# CAN_IC.net
KiCad netlist of a schematic drawn in Altium Designer
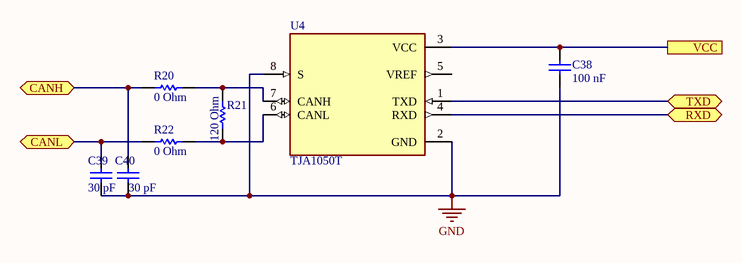
[diagram p0: CAN_IC.SchDoc]

(export (version "E")
  (design (tool "Eeschema 10.0.6"))
  (components
    (comp (ref "C38")
      (value "100 nF")
      (footprint "CAP_0603")
      (description "CAP, size 0603, 100 nF, 50 VDC")
      (fields (field (name "TOLERANCE") "+/-10%"))
      (libsource (lib "Altium_Ceramic_Cap") (part "0106031041050"))
    )
    (comp (ref "C39")
      (value "30 pF")
      (footprint "CAP_0603")
      (description "CAP, size 0603, 33 pF, 50 VDC")
      (fields (field (name "TOLERANCE") "+/-5%"))
      (libsource (lib "Altium_Ceramic_Cap") (part "0106033300550"))
    )
    (comp (ref "C40")
      (value "30 pF")
      (footprint "CAP_0603")
      (description "CAP, size 0603, 33 pF, 50 VDC")
      (fields (field (name "TOLERANCE") "+/-5%"))
      (libsource (lib "Altium_Ceramic_Cap") (part "0106033300550"))
    )
    (comp (ref "R20")
      (value "0 Ohm")
      (footprint "resistor_0603")
      (description "RES, size 0603, 0 Ohm, 1/4 W")
      (libsource (lib "Altium_Resistor") (part "0006030001"))
    )
    (comp (ref "R21")
      (value "120 Ohm")
      (footprint "resistor_0603")
      (description "RES, size 0603, 120 Ohm, 1/4 W")
      (libsource (lib "Altium_Resistor") (part "0006031211"))
    )
    (comp (ref "R22")
      (value "0 Ohm")
      (footprint "resistor_0603")
      (description "RES, size 0603, 0 Ohm, 1/4 W")
      (libsource (lib "Altium_Resistor") (part "0006030001"))
    )
    (comp (ref "U4")
      (value "TJA1050T")
      (footprint "SOIC127P600X175-8N")
      (description "1/1 Transceiver Half CANbus 8-SO")
      (fields (field (name "MF") "NXP USA") (field (name "MP") "TJA1050T/CM,118"))
      (libsource (lib "TJA1050T_CM_118") (part "TJA1050T/CM,118"))
    )
  )
  (nets
    (net (code "1") (name "/CANH") (class "Default")
      (node (ref "C40") (pin "2") (pinfunction "2_2") (pintype "passive"))
      (node (ref "R20") (pin "1") (pinfunction "1_1") (pintype "passive"))
    )
    (net (code "2") (name "/CANL") (class "Default")
      (node (ref "C39") (pin "2") (pinfunction "2_2") (pintype "passive"))
      (node (ref "R22") (pin "1") (pinfunction "1_1") (pintype "passive"))
    )
    (net (code "3") (name "/RXD") (class "Default")
      (node (ref "U4") (pin "4") (pinfunction "RXD_4") (pintype "output"))
    )
    (net (code "4") (name "/TXD") (class "Default")
      (node (ref "U4") (pin "1") (pinfunction "TXD_1") (pintype "input"))
    )
    (net (code "5") (name "/VCC") (class "Default")
      (node (ref "C38") (pin "1") (pinfunction "1_1") (pintype "passive"))
      (node (ref "U4") (pin "3") (pinfunction "VCC_3") (pintype "power_in"))
    )
    (net (code "6") (name "GND") (class "Default")
      (node (ref "C38") (pin "2") (pinfunction "2_2") (pintype "passive"))
      (node (ref "C39") (pin "1") (pinfunction "1_1") (pintype "passive"))
      (node (ref "C40") (pin "1") (pinfunction "1_1") (pintype "passive"))
      (node (ref "U4") (pin "2") (pinfunction "GND_2") (pintype "power_in"))
      (node (ref "U4") (pin "8") (pinfunction "S_8") (pintype "input"))
    )
    (net (code "7") (name "Net-(U4-CANH)") (class "Default")
      (node (ref "R20") (pin "2") (pinfunction "2_2") (pintype "passive"))
      (node (ref "R21") (pin "2") (pinfunction "2_2") (pintype "passive"))
      (node (ref "U4") (pin "7") (pinfunction "CANH_7") (pintype "bidirectional"))
    )
    (net (code "8") (name "Net-(U4-CANL)") (class "Default")
      (node (ref "R21") (pin "1") (pinfunction "1_1") (pintype "passive"))
      (node (ref "R22") (pin "2") (pinfunction "2_2") (pintype "passive"))
      (node (ref "U4") (pin "6") (pinfunction "CANL_6") (pintype "bidirectional"))
    )
    (net (code "9") (name "unconnected-(U4-VREF-Pad5)") (class "Default")
      (node (ref "U4") (pin "5") (pinfunction "VREF_5") (pintype "output"))
    )
  )
)
